# 04_FMC_HPC0.net
KiCad netlist of a schematic drawn in Altium Designer
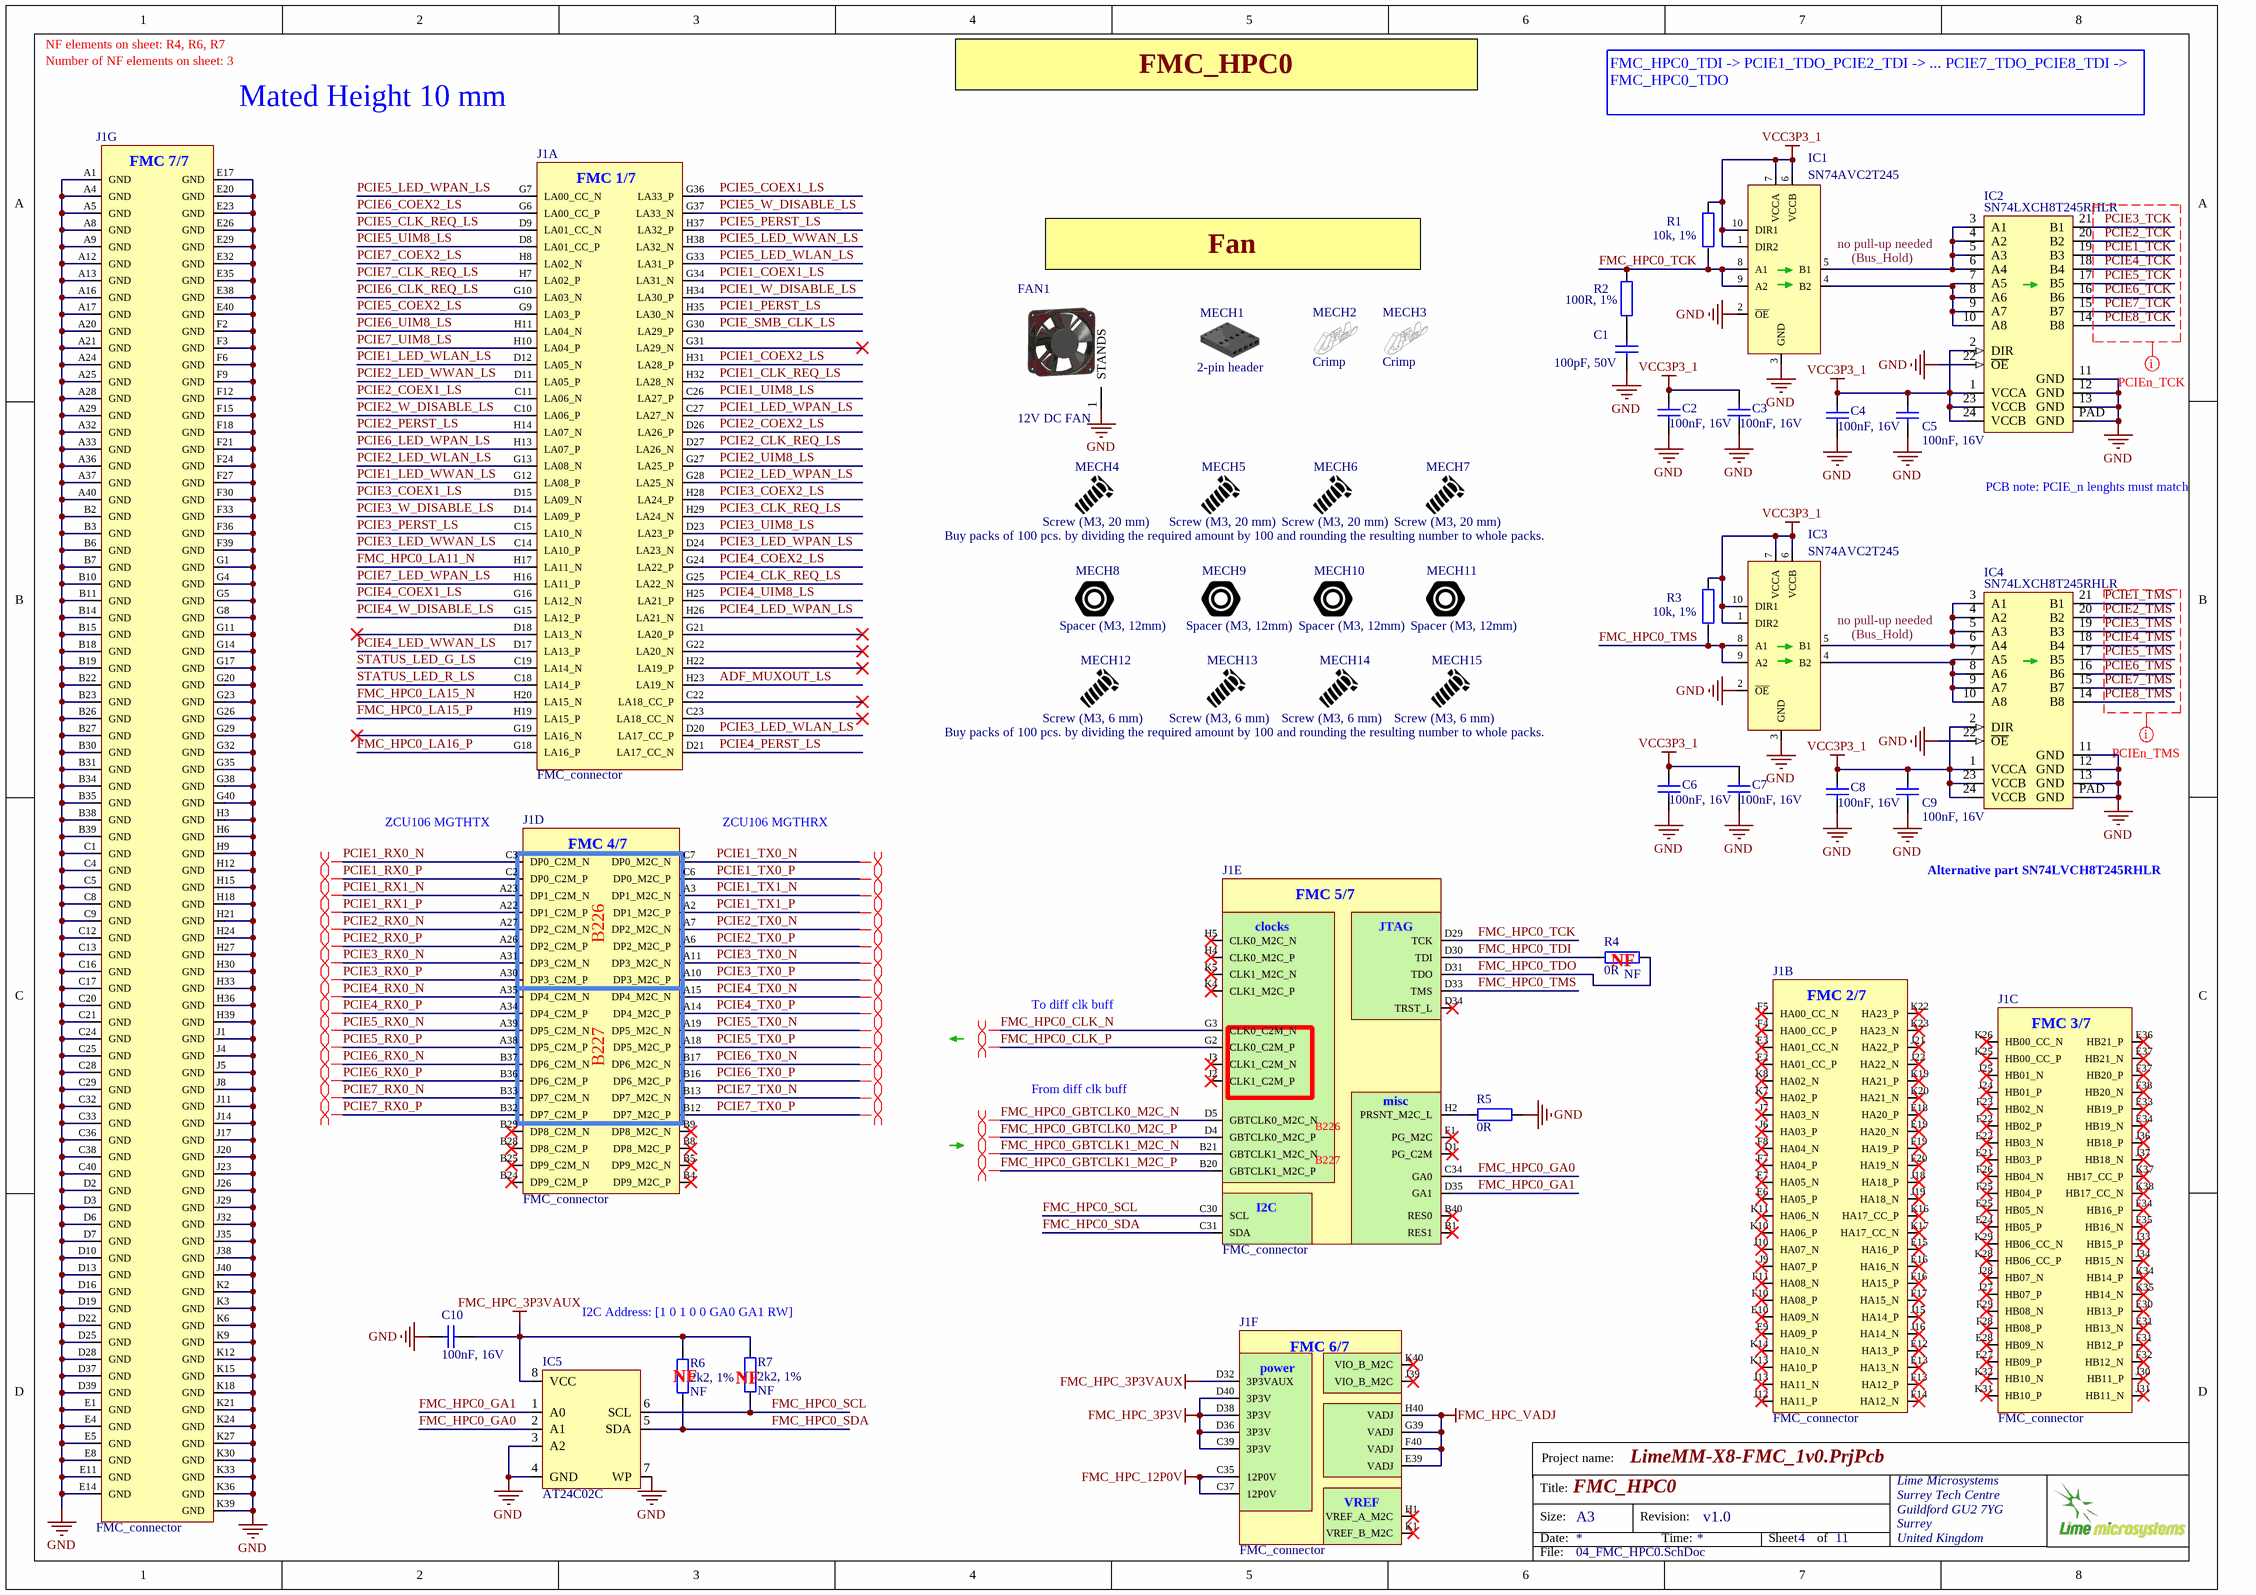
[diagram p0: 04_FMC_HPC0.SchDoc]

(export (version "E")
  (design (tool "Eeschema 10.0.6"))
  (components
    (comp (ref "C1")
      (value "100pF, 50V")
      (footprint "CAP0402")
      (fields (field (name "TOLERANCE") "±5%") (field (name "MANUFACTURER") "Yageo"))
      (libsource (lib "LimeMicroAltiumLib_schLib") (part "Cap_0402"))
    )
    (comp (ref "C2")
      (value "100nF, 16V")
      (footprint "CAP0402")
      (fields (field (name "TOLERANCE") "10 %") (field (name "MANUFACTURER") "Murata Electronics"))
      (libsource (lib "LimeFPGAboard_schLib") (part "Cap_0603"))
    )
    (comp (ref "C3")
      (value "100nF, 16V")
      (footprint "CAP0402")
      (fields (field (name "TOLERANCE") "10 %") (field (name "MANUFACTURER") "Murata Electronics"))
      (libsource (lib "LimeFPGAboard_schLib") (part "Cap_0603"))
    )
    (comp (ref "C4")
      (value "100nF, 16V")
      (footprint "CAP0402")
      (fields (field (name "TOLERANCE") "10 %") (field (name "MANUFACTURER") "Murata Electronics"))
      (libsource (lib "LimeFPGAboard_schLib") (part "Cap_0603"))
    )
    (comp (ref "C5")
      (value "100nF, 16V")
      (footprint "CAP0402")
      (fields (field (name "TOLERANCE") "10 %") (field (name "MANUFACTURER") "Murata Electronics"))
      (libsource (lib "LimeFPGAboard_schLib") (part "Cap_0603"))
    )
    (comp (ref "C6")
      (value "100nF, 16V")
      (footprint "CAP0402")
      (fields (field (name "TOLERANCE") "10 %") (field (name "MANUFACTURER") "Murata Electronics"))
      (libsource (lib "LimeFPGAboard_schLib") (part "Cap_0603"))
    )
    (comp (ref "C7")
      (value "100nF, 16V")
      (footprint "CAP0402")
      (fields (field (name "TOLERANCE") "10 %") (field (name "MANUFACTURER") "Murata Electronics"))
      (libsource (lib "LimeFPGAboard_schLib") (part "Cap_0603"))
    )
    (comp (ref "C8")
      (value "100nF, 16V")
      (footprint "CAP0402")
      (fields (field (name "TOLERANCE") "10 %") (field (name "MANUFACTURER") "Murata Electronics"))
      (libsource (lib "LimeFPGAboard_schLib") (part "Cap_0603"))
    )
    (comp (ref "C9")
      (value "100nF, 16V")
      (footprint "CAP0402")
      (fields (field (name "TOLERANCE") "10 %") (field (name "MANUFACTURER") "Murata Electronics"))
      (libsource (lib "LimeFPGAboard_schLib") (part "Cap_0603"))
    )
    (comp (ref "C10")
      (value "100nF, 16V")
      (footprint "CAP0402")
      (fields (field (name "TOLERANCE") "10 %") (field (name "MANUFACTURER") "Murata Electronics"))
      (libsource (lib "LimeFPGAboard_schLib") (part "Cap_0603"))
    )
    (comp (ref "FAN1")
      (value "12V DC FAN")
      (footprint "FAN_80mm")
      (fields (field (name "MANUFACTURER") "Sunon"))
      (libsource (lib "LimeMicroAltiumLib_schLib_r04") (part "12V_DC_FAN"))
    )
    (comp (ref "IC1")
      (value "SN74AVC2T245")
      (footprint "SN74AVC2T245RSWR")
      (fields (field (name "MANUFACTURER") "Texas Instruments"))
      (libsource (lib "*") (part "SN74AVC2T245"))
    )
    (comp (ref "IC2")
      (value "SN74LXCH8T245RHLR")
      (footprint "SN74LVC8T245RHLR_24-VQFN_LVL_SHIFTER")
      (fields (field (name "MANUFACTURER") "Texas Instruments"))
      (libsource (lib "*") (part "SN74LVC8T245RHLR_LVL_SHIFTER"))
    )
    (comp (ref "IC3")
      (value "SN74AVC2T245")
      (footprint "SN74AVC2T245RSWR")
      (fields (field (name "MANUFACTURER") "Texas Instruments"))
      (libsource (lib "*") (part "SN74AVC2T245"))
    )
    (comp (ref "IC4")
      (value "SN74LXCH8T245RHLR")
      (footprint "SN74LVC8T245RHLR_24-VQFN_LVL_SHIFTER")
      (fields (field (name "MANUFACTURER") "Texas Instruments"))
      (libsource (lib "*") (part "SN74LVC8T245RHLR_LVL_SHIFTER"))
    )
    (comp (ref "IC5")
      (value "AT24C02C")
      (footprint "SOIC127P600-8DL_v2")
      (fields (field (name "MANUFACTURER") "ATMEL"))
      (libsource (lib "LimeMicroAltiumLib_schLib") (part "AT24C02C-SSHM-B"))
    )
    (comp (ref "J1")
      (value "FMC_connector")
      (footprint "FMC_HPC_terminal_conn_ASP-134488-01")
      (fields (field (name "MANUFACTURER") "Samtec"))
      (libsource (lib "LimeMicroAltiumLib") (part "FMC_connector"))
    )
    (comp (ref "MECH1")
      (value "2-pin header")
      (fields (field (name "MANUFACTURER") "Molex"))
      (libsource (lib "LimeMicroAltiumLib_schLib_r05") (part "Universal_crimped_header"))
    )
    (comp (ref "MECH2")
      (value "Crimp")
      (fields (field (name "MANUFACTURER") "Molex"))
      (libsource (lib "LimeMicroAltiumLib_schLib_r05") (part "Universal_crimp"))
    )
    (comp (ref "MECH3")
      (value "Crimp")
      (fields (field (name "MANUFACTURER") "Molex"))
      (libsource (lib "LimeMicroAltiumLib_schLib_r05") (part "Universal_crimp"))
    )
    (comp (ref "MECH4")
      (value "Screw (M3, 20 mm)")
      (fields (field (name "MANUFACTURER") "TR Fastenings"))
      (libsource (lib "LimeMicroAltiumLib_schLib_r05") (part "Universal_mech_screw"))
    )
    (comp (ref "MECH5")
      (value "Screw (M3, 20 mm)")
      (fields
        (field (name "ASSEMBLY INFO") "Buy packs of 100 pcs. by dividing the required amount by 100 and rounding the resulting number to whole packs.")
        (field (name "MANUFACTURER") "TR Fastenings")
      )
      (libsource (lib "LimeMicroAltiumLib_schLib_r05") (part "Universal_mech_screw"))
    )
    (comp (ref "MECH6")
      (value "Screw (M3, 20 mm)")
      (fields (field (name "MANUFACTURER") "TR Fastenings"))
      (libsource (lib "LimeMicroAltiumLib_schLib_r05") (part "Universal_mech_screw"))
    )
    (comp (ref "MECH7")
      (value "Screw (M3, 20 mm)")
      (fields (field (name "MANUFACTURER") "TR Fastenings"))
      (libsource (lib "LimeMicroAltiumLib_schLib_r05") (part "Universal_mech_screw"))
    )
    (comp (ref "MECH8")
      (value "Spacer (M3, 12mm)")
      (fields (field (name "MANUFACTURER") "ETTINGER"))
      (libsource (lib "LimeMicroAltiumLib_schLib_r05") (part "Universal_mech_nut"))
    )
    (comp (ref "MECH9")
      (value "Spacer (M3, 12mm)")
      (fields (field (name "MANUFACTURER") "ETTINGER"))
      (libsource (lib "LimeMicroAltiumLib_schLib_r05") (part "Universal_mech_nut"))
    )
    (comp (ref "MECH10")
      (value "Spacer (M3, 12mm)")
      (fields (field (name "MANUFACTURER") "ETTINGER"))
      (libsource (lib "LimeMicroAltiumLib_schLib_r05") (part "Universal_mech_nut"))
    )
    (comp (ref "MECH11")
      (value "Spacer (M3, 12mm)")
      (fields (field (name "MANUFACTURER") "ETTINGER"))
      (libsource (lib "LimeMicroAltiumLib_schLib_r05") (part "Universal_mech_nut"))
    )
    (comp (ref "MECH12")
      (value "Screw (M3, 6 mm)")
      (fields (field (name "MANUFACTURER") "TR Fastenings"))
      (libsource (lib "LimeMicroAltiumLib_schLib_r05") (part "Universal_mech_screw"))
    )
    (comp (ref "MECH13")
      (value "Screw (M3, 6 mm)")
      (fields
        (field (name "ASSEMBLY INFO") "Buy packs of 100 pcs. by dividing the required amount by 100 and rounding the resulting number to whole packs.")
        (field (name "MANUFACTURER") "TR Fastenings")
      )
      (libsource (lib "LimeMicroAltiumLib_schLib_r05") (part "Universal_mech_screw"))
    )
    (comp (ref "MECH14")
      (value "Screw (M3, 6 mm)")
      (fields (field (name "MANUFACTURER") "TR Fastenings"))
      (libsource (lib "LimeMicroAltiumLib_schLib_r05") (part "Universal_mech_screw"))
    )
    (comp (ref "MECH15")
      (value "Screw (M3, 6 mm)")
      (fields (field (name "MANUFACTURER") "TR Fastenings"))
      (libsource (lib "LimeMicroAltiumLib_schLib_r05") (part "Universal_mech_screw"))
    )
    (comp (ref "R1")
      (value "10k, 1%")
      (footprint "RES0402")
      (fields (field (name "MANUFACTURER") "Yageo") (field (name "TOLERANCE") "±1%"))
      (libsource (lib "LimeMicroAltiumLib_schLib") (part "Res_0402"))
    )
    (comp (ref "R2")
      (value "100R, 1%")
      (footprint "RES0402")
      (fields (field (name "TOLERANCE") "±1%") (field (name "MANUFACTURER") "Stackpole Electronics Inc."))
      (libsource (lib "LimeFPGAboard_schLib") (part "Res_0402"))
    )
    (comp (ref "R3")
      (value "10k, 1%")
      (footprint "RES0402")
      (fields (field (name "MANUFACTURER") "Yageo") (field (name "TOLERANCE") "±1%"))
      (libsource (lib "LimeMicroAltiumLib_schLib") (part "Res_0402"))
    )
    (comp (ref "R4")
      (value "0R")
      (footprint "RES0402")
      (fields
        (field (name "ASSEMBLY INFO") "NF")
        (field (name "MANUFACTURER") "Yageo")
        (field (name "TOLERANCE") "Jumper")
      )
      (libsource (lib "") (part "Res_0402_1"))
    )
    (comp (ref "R5")
      (value "0R")
      (footprint "RES0402")
      (fields (field (name "MANUFACTURER") "Yageo") (field (name "TOLERANCE") "Jumper"))
      (libsource (lib "LimeMicroAltiumLib_schLib") (part "Res_0402"))
    )
    (comp (ref "R6")
      (value "2k2, 1%")
      (footprint "RES0402")
      (fields
        (field (name "ASSEMBLY INFO") "NF")
        (field (name "MANUFACTURER") "Stackpole Electronics Inc")
        (field (name "TOLERANCE") "±1%")
      )
      (libsource (lib "") (part "Res_0402_1"))
    )
    (comp (ref "R7")
      (value "2k2, 1%")
      (footprint "RES0402")
      (fields
        (field (name "ASSEMBLY INFO") "NF")
        (field (name "MANUFACTURER") "Stackpole Electronics Inc")
        (field (name "TOLERANCE") "±1%")
      )
      (libsource (lib "") (part "Res_0402_1"))
    )
  )
  (nets
    (net (code "1") (name "/ADF_MUXOUT_LS") (class "Default")
      (node (ref "J1") (pin "H23") (pinfunction "LA19_N_H23") (pintype "passive"))
    )
    (net (code "2") (name "/FMC_HPC0_CLK_N") (class "Default")
      (node (ref "J1") (pin "G3") (pinfunction "CLK0_C2M_N_G3") (pintype "passive"))
    )
    (net (code "3") (name "/FMC_HPC0_CLK_P") (class "Default")
      (node (ref "J1") (pin "G2") (pinfunction "CLK0_C2M_P_G2") (pintype "passive"))
    )
    (net (code "4") (name "/FMC_HPC0_GA0") (class "Default")
      (node (ref "IC5") (pin "2") (pinfunction "A1_2") (pintype "passive"))
      (node (ref "J1") (pin "C34") (pinfunction "GA0_C34") (pintype "passive"))
    )
    (net (code "5") (name "/FMC_HPC0_GA1") (class "Default")
      (node (ref "IC5") (pin "1") (pinfunction "A0_1") (pintype "passive"))
      (node (ref "J1") (pin "D35") (pinfunction "GA1_D35") (pintype "passive"))
    )
    (net (code "6") (name "/FMC_HPC0_GBTCLK0_M2C_N") (class "Default")
      (node (ref "J1") (pin "D5") (pinfunction "GBTCLK0_M2C_N_D5") (pintype "passive"))
    )
    (net (code "7") (name "/FMC_HPC0_GBTCLK0_M2C_P") (class "Default")
      (node (ref "J1") (pin "D4") (pinfunction "GBTCLK0_M2C_P_D4") (pintype "passive"))
    )
    (net (code "8") (name "/FMC_HPC0_GBTCLK1_M2C_N") (class "Default")
      (node (ref "J1") (pin "B21") (pinfunction "GBTCLK1_M2C_N_B21") (pintype "passive"))
    )
    (net (code "9") (name "/FMC_HPC0_GBTCLK1_M2C_P") (class "Default")
      (node (ref "J1") (pin "B20") (pinfunction "GBTCLK1_M2C_P_B20") (pintype "passive"))
    )
    (net (code "10") (name "/FMC_HPC0_LA11_N") (class "Default")
      (node (ref "J1") (pin "H17") (pinfunction "LA11_N_H17") (pintype "passive"))
    )
    (net (code "11") (name "/FMC_HPC0_LA15_N") (class "Default")
      (node (ref "J1") (pin "H20") (pinfunction "LA15_N_H20") (pintype "passive"))
    )
    (net (code "12") (name "/FMC_HPC0_LA15_P") (class "Default")
      (node (ref "J1") (pin "H19") (pinfunction "LA15_P_H19") (pintype "passive"))
    )
    (net (code "13") (name "/FMC_HPC0_LA16_P") (class "Default")
      (node (ref "J1") (pin "G18") (pinfunction "LA16_P_G18") (pintype "passive"))
    )
    (net (code "14") (name "/FMC_HPC0_SCL") (class "Default")
      (node (ref "IC5") (pin "6") (pinfunction "SCL_6") (pintype "passive"))
      (node (ref "J1") (pin "C30") (pinfunction "SCL_C30") (pintype "passive"))
      (node (ref "R7") (pin "2") (pinfunction "2_2") (pintype "passive"))
    )
    (net (code "15") (name "/FMC_HPC0_SDA") (class "Default")
      (node (ref "IC5") (pin "5") (pinfunction "SDA_5") (pintype "passive"))
      (node (ref "J1") (pin "C31") (pinfunction "SDA_C31") (pintype "passive"))
      (node (ref "R6") (pin "2") (pinfunction "2_2") (pintype "passive"))
    )
    (net (code "16") (name "/FMC_HPC0_TCK") (class "Default")
      (node (ref "IC1") (pin "8") (pinfunction "A1_8") (pintype "passive"))
      (node (ref "IC1") (pin "9") (pinfunction "A2_9") (pintype "passive"))
      (node (ref "J1") (pin "D29") (pinfunction "TCK_D29") (pintype "passive"))
      (node (ref "R1") (pin "2") (pinfunction "2_2") (pintype "passive"))
      (node (ref "R2") (pin "2") (pinfunction "2_2") (pintype "passive"))
    )
    (net (code "17") (name "/FMC_HPC0_TDI") (class "Default")
      (node (ref "J1") (pin "D30") (pinfunction "TDI_D30") (pintype "passive"))
      (node (ref "R4") (pin "2") (pinfunction "2_2") (pintype "passive"))
    )
    (net (code "18") (name "/FMC_HPC0_TDO") (class "Default")
      (node (ref "J1") (pin "D31") (pinfunction "TDO_D31") (pintype "passive"))
      (node (ref "R4") (pin "1") (pinfunction "1_1") (pintype "passive"))
    )
    (net (code "19") (name "/FMC_HPC0_TMS") (class "Default")
      (node (ref "IC3") (pin "8") (pinfunction "A1_8") (pintype "passive"))
      (node (ref "IC3") (pin "9") (pinfunction "A2_9") (pintype "passive"))
      (node (ref "J1") (pin "D33") (pinfunction "TMS_D33") (pintype "passive"))
      (node (ref "R3") (pin "2") (pinfunction "2_2") (pintype "passive"))
    )
    (net (code "20") (name "/PCIE1_CLK_REQ_LS") (class "Default")
      (node (ref "J1") (pin "H32") (pinfunction "LA28_N_H32") (pintype "passive"))
    )
    (net (code "21") (name "/PCIE1_COEX1_LS") (class "Default")
      (node (ref "J1") (pin "G34") (pinfunction "LA31_N_G34") (pintype "passive"))
    )
    (net (code "22") (name "/PCIE1_COEX2_LS") (class "Default")
      (node (ref "J1") (pin "H31") (pinfunction "LA28_P_H31") (pintype "passive"))
    )
    (net (code "23") (name "/PCIE1_LED_WLAN_LS") (class "Default")
      (node (ref "J1") (pin "D12") (pinfunction "LA05_N_D12") (pintype "passive"))
    )
    (net (code "24") (name "/PCIE1_LED_WPAN_LS") (class "Default")
      (node (ref "J1") (pin "C27") (pinfunction "LA27_N_C27") (pintype "passive"))
    )
    (net (code "25") (name "/PCIE1_LED_WWAN_LS") (class "Default")
      (node (ref "J1") (pin "G12") (pinfunction "LA08_P_G12") (pintype "passive"))
    )
    (net (code "26") (name "/PCIE1_PERST_LS") (class "Default")
      (node (ref "J1") (pin "H35") (pinfunction "LA30_N_H35") (pintype "passive"))
    )
    (net (code "27") (name "/PCIE1_RX0_N") (class "Default")
      (node (ref "J1") (pin "C3") (pinfunction "DP0_C2M_N_C3") (pintype "passive"))
    )
    (net (code "28") (name "/PCIE1_RX0_P") (class "Default")
      (node (ref "J1") (pin "C2") (pinfunction "DP0_C2M_P_C2") (pintype "passive"))
    )
    (net (code "29") (name "/PCIE1_RX1_N") (class "Default")
      (node (ref "J1") (pin "A23") (pinfunction "DP1_C2M_N_A23") (pintype "passive"))
    )
    (net (code "30") (name "/PCIE1_RX1_P") (class "Default")
      (node (ref "J1") (pin "A22") (pinfunction "DP1_C2M_P_A22") (pintype "passive"))
    )
    (net (code "31") (name "/PCIE1_TCK") (class "Default")
      (node (ref "IC2") (pin "19") (pinfunction "B3_19") (pintype "bidirectional"))
    )
    (net (code "32") (name "/PCIE1_TMS") (class "Default")
      (node (ref "IC4") (pin "21") (pinfunction "B1_21") (pintype "bidirectional"))
    )
    (net (code "33") (name "/PCIE1_TX0_N") (class "Default")
      (node (ref "J1") (pin "C7") (pinfunction "DP0_M2C_N_C7") (pintype "passive"))
    )
    (net (code "34") (name "/PCIE1_TX0_P") (class "Default")
      (node (ref "J1") (pin "C6") (pinfunction "DP0_M2C_P_C6") (pintype "passive"))
    )
    (net (code "35") (name "/PCIE1_TX1_N") (class "Default")
      (node (ref "J1") (pin "A3") (pinfunction "DP1_M2C_N_A3") (pintype "passive"))
    )
    (net (code "36") (name "/PCIE1_TX1_P") (class "Default")
      (node (ref "J1") (pin "A2") (pinfunction "DP1_M2C_P_A2") (pintype "passive"))
    )
    (net (code "37") (name "/PCIE1_UIM8_LS") (class "Default")
      (node (ref "J1") (pin "C26") (pinfunction "LA27_P_C26") (pintype "passive"))
    )
    (net (code "38") (name "/PCIE1_W_DISABLE_LS") (class "Default")
      (node (ref "J1") (pin "H34") (pinfunction "LA30_P_H34") (pintype "passive"))
    )
    (net (code "39") (name "/PCIE2_CLK_REQ_LS") (class "Default")
      (node (ref "J1") (pin "D27") (pinfunction "LA26_N_D27") (pintype "passive"))
    )
    (net (code "40") (name "/PCIE2_COEX1_LS") (class "Default")
      (node (ref "J1") (pin "C11") (pinfunction "LA06_N_C11") (pintype "passive"))
    )
    (net (code "41") (name "/PCIE2_COEX2_LS") (class "Default")
      (node (ref "J1") (pin "D26") (pinfunction "LA26_P_D26") (pintype "passive"))
    )
    (net (code "42") (name "/PCIE2_LED_WLAN_LS") (class "Default")
      (node (ref "J1") (pin "G13") (pinfunction "LA08_N_G13") (pintype "passive"))
    )
    (net (code "43") (name "/PCIE2_LED_WPAN_LS") (class "Default")
      (node (ref "J1") (pin "G28") (pinfunction "LA25_N_G28") (pintype "passive"))
    )
    (net (code "44") (name "/PCIE2_LED_WWAN_LS") (class "Default")
      (node (ref "J1") (pin "D11") (pinfunction "LA05_P_D11") (pintype "passive"))
    )
    (net (code "45") (name "/PCIE2_PERST_LS") (class "Default")
      (node (ref "J1") (pin "H14") (pinfunction "LA07_N_H14") (pintype "passive"))
    )
    (net (code "46") (name "/PCIE2_RX0_N") (class "Default")
      (node (ref "J1") (pin "A27") (pinfunction "DP2_C2M_N_A27") (pintype "passive"))
    )
    (net (code "47") (name "/PCIE2_RX0_P") (class "Default")
      (node (ref "J1") (pin "A26") (pinfunction "DP2_C2M_P_A26") (pintype "passive"))
    )
    (net (code "48") (name "/PCIE2_TCK") (class "Default")
      (node (ref "IC2") (pin "20") (pinfunction "B2_20") (pintype "bidirectional"))
    )
    (net (code "49") (name "/PCIE2_TMS") (class "Default")
      (node (ref "IC4") (pin "20") (pinfunction "B2_20") (pintype "bidirectional"))
    )
    (net (code "50") (name "/PCIE2_TX0_N") (class "Default")
      (node (ref "J1") (pin "A7") (pinfunction "DP2_M2C_N_A7") (pintype "passive"))
    )
    (net (code "51") (name "/PCIE2_TX0_P") (class "Default")
      (node (ref "J1") (pin "A6") (pinfunction "DP2_M2C_P_A6") (pintype "passive"))
    )
    (net (code "52") (name "/PCIE2_UIM8_LS") (class "Default")
      (node (ref "J1") (pin "G27") (pinfunction "LA25_P_G27") (pintype "passive"))
    )
    (net (code "53") (name "/PCIE2_W_DISABLE_LS") (class "Default")
      (node (ref "J1") (pin "C10") (pinfunction "LA06_P_C10") (pintype "passive"))
    )
    (net (code "54") (name "/PCIE3_CLK_REQ_LS") (class "Default")
      (node (ref "J1") (pin "H29") (pinfunction "LA24_N_H29") (pintype "passive"))
    )
    (net (code "55") (name "/PCIE3_COEX1_LS") (class "Default")
      (node (ref "J1") (pin "D15") (pinfunction "LA09_N_D15") (pintype "passive"))
    )
    (net (code "56") (name "/PCIE3_COEX2_LS") (class "Default")
      (node (ref "J1") (pin "H28") (pinfunction "LA24_P_H28") (pintype "passive"))
    )
    (net (code "57") (name "/PCIE3_LED_WLAN_LS") (class "Default")
      (node (ref "J1") (pin "D20") (pinfunction "LA17_CC_P_D20") (pintype "passive"))
    )
    (net (code "58") (name "/PCIE3_LED_WPAN_LS") (class "Default")
      (node (ref "J1") (pin "D24") (pinfunction "LA23_N_D24") (pintype "passive"))
    )
    (net (code "59") (name "/PCIE3_LED_WWAN_LS") (class "Default")
      (node (ref "J1") (pin "C14") (pinfunction "LA10_P_C14") (pintype "passive"))
    )
    (net (code "60") (name "/PCIE3_PERST_LS") (class "Default")
      (node (ref "J1") (pin "C15") (pinfunction "LA10_N_C15") (pintype "passive"))
    )
    (net (code "61") (name "/PCIE3_RX0_N") (class "Default")
      (node (ref "J1") (pin "A31") (pinfunction "DP3_C2M_N_A31") (pintype "passive"))
    )
    (net (code "62") (name "/PCIE3_RX0_P") (class "Default")
      (node (ref "J1") (pin "A30") (pinfunction "DP3_C2M_P_A30") (pintype "passive"))
    )
    (net (code "63") (name "/PCIE3_TCK") (class "Default")
      (node (ref "IC2") (pin "21") (pinfunction "B1_21") (pintype "bidirectional"))
    )
    (net (code "64") (name "/PCIE3_TMS") (class "Default")
      (node (ref "IC4") (pin "19") (pinfunction "B3_19") (pintype "bidirectional"))
    )
    (net (code "65") (name "/PCIE3_TX0_N") (class "Default")
      (node (ref "J1") (pin "A11") (pinfunction "DP3_M2C_N_A11") (pintype "passive"))
    )
    (net (code "66") (name "/PCIE3_TX0_P") (class "Default")
      (node (ref "J1") (pin "A10") (pinfunction "DP3_M2C_P_A10") (pintype "passive"))
    )
    (net (code "67") (name "/PCIE3_UIM8_LS") (class "Default")
      (node (ref "J1") (pin "D23") (pinfunction "LA23_P_D23") (pintype "passive"))
    )
    (net (code "68") (name "/PCIE3_W_DISABLE_LS") (class "Default")
      (node (ref "J1") (pin "D14") (pinfunction "LA09_P_D14") (pintype "passive"))
    )
    (net (code "69") (name "/PCIE4_CLK_REQ_LS") (class "Default")
      (node (ref "J1") (pin "G25") (pinfunction "LA22_N_G25") (pintype "passive"))
    )
    (net (code "70") (name "/PCIE4_COEX1_LS") (class "Default")
      (node (ref "J1") (pin "G16") (pinfunction "LA12_N_G16") (pintype "passive"))
    )
    (net (code "71") (name "/PCIE4_COEX2_LS") (class "Default")
      (node (ref "J1") (pin "G24") (pinfunction "LA22_P_G24") (pintype "passive"))
    )
    (net (code "72") (name "/PCIE4_LED_WPAN_LS") (class "Default")
      (node (ref "J1") (pin "H26") (pinfunction "LA21_N_H26") (pintype "passive"))
    )
    (net (code "73") (name "/PCIE4_LED_WWAN_LS") (class "Default")
      (node (ref "J1") (pin "D17") (pinfunction "LA13_P_D17") (pintype "passive"))
    )
    (net (code "74") (name "/PCIE4_PERST_LS") (class "Default")
      (node (ref "J1") (pin "D21") (pinfunction "LA17_CC_N_D21") (pintype "passive"))
    )
    (net (code "75") (name "/PCIE4_RX0_N") (class "Default")
      (node (ref "J1") (pin "A35") (pinfunction "DP4_C2M_N_A35") (pintype "passive"))
    )
    (net (code "76") (name "/PCIE4_RX0_P") (class "Default")
      (node (ref "J1") (pin "A34") (pinfunction "DP4_C2M_P_A34") (pintype "passive"))
    )
    (net (code "77") (name "/PCIE4_TCK") (class "Default")
      (node (ref "IC2") (pin "18") (pinfunction "B4_18") (pintype "bidirectional"))
    )
    (net (code "78") (name "/PCIE4_TMS") (class "Default")
      (node (ref "IC4") (pin "18") (pinfunction "B4_18") (pintype "bidirectional"))
    )
    (net (code "79") (name "/PCIE4_TX0_N") (class "Default")
      (node (ref "J1") (pin "A15") (pinfunction "DP4_M2C_N_A15") (pintype "passive"))
    )
    (net (code "80") (name "/PCIE4_TX0_P") (class "Default")
      (node (ref "J1") (pin "A14") (pinfunction "DP4_M2C_P_A14") (pintype "passive"))
    )
    (net (code "81") (name "/PCIE4_UIM8_LS") (class "Default")
      (node (ref "J1") (pin "H25") (pinfunction "LA21_P_H25") (pintype "passive"))
    )
    (net (code "82") (name "/PCIE4_W_DISABLE_LS") (class "Default")
      (node (ref "J1") (pin "G15") (pinfunction "LA12_P_G15") (pintype "passive"))
    )
    (net (code "83") (name "/PCIE5_CLK_REQ_LS") (class "Default")
      (node (ref "J1") (pin "D9") (pinfunction "LA01_CC_N_D9") (pintype "passive"))
    )
    (net (code "84") (name "/PCIE5_COEX1_LS") (class "Default")
      (node (ref "J1") (pin "G36") (pinfunction "LA33_P_G36") (pintype "passive"))
    )
    (net (code "85") (name "/PCIE5_COEX2_LS") (class "Default")
      (node (ref "J1") (pin "G9") (pinfunction "LA03_P_G9") (pintype "passive"))
    )
    (net (code "86") (name "/PCIE5_LED_WLAN_LS") (class "Default")
      (node (ref "J1") (pin "G33") (pinfunction "LA31_P_G33") (pintype "passive"))
    )
    (net (code "87") (name "/PCIE5_LED_WPAN_LS") (class "Default")
      (node (ref "J1") (pin "G7") (pinfunction "LA00_CC_N_G7") (pintype "passive"))
    )
    (net (code "88") (name "/PCIE5_LED_WWAN_LS") (class "Default")
      (node (ref "J1") (pin "H38") (pinfunction "LA32_N_H38") (pintype "passive"))
    )
    (net (code "89") (name "/PCIE5_PERST_LS") (class "Default")
      (node (ref "J1") (pin "H37") (pinfunction "LA32_P_H37") (pintype "passive"))
    )
    (net (code "90") (name "/PCIE5_RX0_N") (class "Default")
      (node (ref "J1") (pin "A39") (pinfunction "DP5_C2M_N_A39") (pintype "passive"))
    )
    (net (code "91") (name "/PCIE5_RX0_P") (class "Default")
      (node (ref "J1") (pin "A38") (pinfunction "DP5_C2M_P_A38") (pintype "passive"))
    )
    (net (code "92") (name "/PCIE5_TCK") (class "Default")
      (node (ref "IC2") (pin "17") (pinfunction "B5_17") (pintype "bidirectional"))
    )
    (net (code "93") (name "/PCIE5_TMS") (class "Default")
      (node (ref "IC4") (pin "17") (pinfunction "B5_17") (pintype "bidirectional"))
    )
    (net (code "94") (name "/PCIE5_TX0_N") (class "Default")
      (node (ref "J1") (pin "A19") (pinfunction "DP5_M2C_N_A19") (pintype "passive"))
    )
    (net (code "95") (name "/PCIE5_TX0_P") (class "Default")
      (node (ref "J1") (pin "A18") (pinfunction "DP5_M2C_P_A18") (pintype "passive"))
    )
    (net (code "96") (name "/PCIE5_UIM8_LS") (class "Default")
      (node (ref "J1") (pin "D8") (pinfunction "LA01_CC_P_D8") (pintype "passive"))
    )
    (net (code "97") (name "/PCIE5_W_DISABLE_LS") (class "Default")
      (node (ref "J1") (pin "G37") (pinfunction "LA33_N_G37") (pintype "passive"))
    )
    (net (code "98") (name "/PCIE6_CLK_REQ_LS") (class "Default")
      (node (ref "J1") (pin "G10") (pinfunction "LA03_N_G10") (pintype "passive"))
    )
    (net (code "99") (name "/PCIE6_COEX2_LS") (class "Default")
      (node (ref "J1") (pin "G6") (pinfunction "LA00_CC_P_G6") (pintype "passive"))
    )
    (net (code "100") (name "/PCIE6_LED_WPAN_LS") (class "Default")
      (node (ref "J1") (pin "H13") (pinfunction "LA07_P_H13") (pintype "passive"))
    )
    (net (code "101") (name "/PCIE6_RX0_N") (class "Default")
      (node (ref "J1") (pin "B37") (pinfunction "DP6_C2M_N_B37") (pintype "passive"))
    )
    (net (code "102") (name "/PCIE6_RX0_P") (class "Default")
      (node (ref "J1") (pin "B36") (pinfunction "DP6_C2M_P_B36") (pintype "passive"))
    )
    (net (code "103") (name "/PCIE6_TCK") (class "Default")
      (node (ref "IC2") (pin "16") (pinfunction "B6_16") (pintype "bidirectional"))
    )
    (net (code "104") (name "/PCIE6_TMS") (class "Default")
      (node (ref "IC4") (pin "16") (pinfunction "B6_16") (pintype "bidirectional"))
    )
    (net (code "105") (name "/PCIE6_TX0_N") (class "Default")
      (node (ref "J1") (pin "B17") (pinfunction "DP6_M2C_N_B17") (pintype "passive"))
    )
    (net (code "106") (name "/PCIE6_TX0_P") (class "Default")
      (node (ref "J1") (pin "B16") (pinfunction "DP6_M2C_P_B16") (pintype "passive"))
    )
    (net (code "107") (name "/PCIE6_UIM8_LS") (class "Default")
      (node (ref "J1") (pin "H11") (pinfunction "LA04_N_H11") (pintype "passive"))
    )
    (net (code "108") (name "/PCIE7_CLK_REQ_LS") (class "Default")
      (node (ref "J1") (pin "H7") (pinfunction "LA02_P_H7") (pintype "passive"))
    )
    (net (code "109") (name "/PCIE7_COEX2_LS") (class "Default")
      (node (ref "J1") (pin "H8") (pinfunction "LA02_N_H8") (pintype "passive"))
    )
    (net (code "110") (name "/PCIE7_LED_WPAN_LS") (class "Default")
      (node (ref "J1") (pin "H16") (pinfunction "LA11_P_H16") (pintype "passive"))
    )
    (net (code "111") (name "/PCIE7_RX0_N") (class "Default")
      (node (ref "J1") (pin "B33") (pinfunction "DP7_C2M_N_B33") (pintype "passive"))
    )
    (net (code "112") (name "/PCIE7_RX0_P") (class "Default")
      (node (ref "J1") (pin "B32") (pinfunction "DP7_C2M_P_B32") (pintype "passive"))
    )
    (net (code "113") (name "/PCIE7_TCK") (class "Default")
      (node (ref "IC2") (pin "15") (pinfunction "B7_15") (pintype "bidirectional"))
    )
    (net (code "114") (name "/PCIE7_TMS") (class "Default")
      (node (ref "IC4") (pin "15") (pinfunction "B7_15") (pintype "bidirectional"))
    )
    (net (code "115") (name "/PCIE7_TX0_N") (class "Default")
      (node (ref "J1") (pin "B13") (pinfunction "DP7_M2C_N_B13") (pintype "passive"))
    )
    (net (code "116") (name "/PCIE7_TX0_P") (class "Default")
      (node (ref "J1") (pin "B12") (pinfunction "DP7_M2C_P_B12") (pintype "passive"))
    )
    (net (code "117") (name "/PCIE7_UIM8_LS") (class "Default")
      (node (ref "J1") (pin "H10") (pinfunction "LA04_P_H10") (pintype "passive"))
    )
    (net (code "118") (name "/PCIE8_TCK") (class "Default")
      (node (ref "IC2") (pin "14") (pinfunction "B8_14") (pintype "bidirectional"))
    )
    (net (code "119") (name "/PCIE8_TMS") (class "Default")
      (node (ref "IC4") (pin "14") (pinfunction "B8_14") (pintype "bidirectional"))
    )
    (net (code "120") (name "/PCIE_SMB_CLK_LS") (class "Default")
      (node (ref "J1") (pin "G30") (pinfunction "LA29_P_G30") (pintype "passive"))
    )
    (net (code "121") (name "/STATUS_LED_G_LS") (class "Default")
      (node (ref "J1") (pin "C19") (pinfunction "LA14_N_C19") (pintype "passive"))
    )
    (net (code "122") (name "/STATUS_LED_R_LS") (class "Default")
      (node (ref "J1") (pin "C18") (pinfunction "LA14_P_C18") (pintype "passive"))
    )
    (net (code "123") (name "FMC_HPC_3P3V") (class "Default")
      (node (ref "J1") (pin "C39") (pinfunction "3P3V_C39") (pintype "passive"))
      (node (ref "J1") (pin "D36") (pinfunction "3P3V_D36") (pintype "passive"))
      (node (ref "J1") (pin "D38") (pinfunction "3P3V_D38") (pintype "passive"))
      (node (ref "J1") (pin "D40") (pinfunction "3P3V_D40") (pintype "passive"))
    )
    (net (code "124") (name "FMC_HPC_3P3VAUX") (class "Default")
      (node (ref "C10") (pin "1") (pinfunction "1_1") (pintype "passive"))
      (node (ref "IC5") (pin "8") (pinfunction "VCC_8") (pintype "passive"))
      (node (ref "J1") (pin "D32") (pinfunction "3P3VAUX_D32") (pintype "passive"))
      (node (ref "R6") (pin "1") (pinfunction "1_1") (pintype "passive"))
      (node (ref "R7") (pin "1") (pinfunction "1_1") (pintype "passive"))
    )
    (net (code "125") (name "FMC_HPC_12P0V") (class "Default")
      (node (ref "J1") (pin "C35") (pinfunction "12P0V_C35") (pintype "passive"))
      (node (ref "J1") (pin "C37") (pinfunction "12P0V_C37") (pintype "passive"))
    )
    (net (code "126") (name "FMC_HPC_VADJ") (class "Default")
      (node (ref "J1") (pin "E39") (pinfunction "VADJ_E39") (pintype "passive"))
      (node (ref "J1") (pin "F40") (pinfunction "VADJ_F40") (pintype "passive"))
      (node (ref "J1") (pin "G39") (pinfunction "VADJ_G39") (pintype "passive"))
      (node (ref "J1") (pin "H40") (pinfunction "VADJ_H40") (pintype "passive"))
    )
    (net (code "127") (name "GND") (class "Default")
      (node (ref "C1") (pin "2") (pinfunction "2_2") (pintype "passive"))
      (node (ref "C10") (pin "2") (pinfunction "2_2") (pintype "passive"))
      (node (ref "C2") (pin "1") (pinfunction "1_1") (pintype "passive"))
      (node (ref "C3") (pin "1") (pinfunction "1_1") (pintype "passive"))
      (node (ref "C4") (pin "1") (pinfunction "1_1") (pintype "passive"))
      (node (ref "C5") (pin "1") (pinfunction "1_1") (pintype "passive"))
      (node (ref "C6") (pin "1") (pinfunction "1_1") (pintype "passive"))
      (node (ref "C7") (pin "1") (pinfunction "1_1") (pintype "passive"))
      (node (ref "C8") (pin "1") (pinfunction "1_1") (pintype "passive"))
      (node (ref "C9") (pin "1") (pinfunction "1_1") (pintype "passive"))
      (node (ref "FAN1") (pin "1") (pinfunction "STANDS_1") (pintype "passive"))
      (node (ref "IC1") (pin "2") (pinfunction "~{OE}_2") (pintype "passive"))
      (node (ref "IC1") (pin "3") (pinfunction "GND_3") (pintype "passive"))
      (node (ref "IC2") (pin "11") (pinfunction "GND_11") (pintype "passive"))
      (node (ref "IC2") (pin "12") (pinfunction "GND_12") (pintype "passive"))
      (node (ref "IC2") (pin "13") (pinfunction "GND_13") (pintype "passive"))
      (node (ref "IC2") (pin "22") (pinfunction "~{OE}_22") (pintype "input"))
      (node (ref "IC2") (pin "PAD") (pinfunction "GND_PAD") (pintype "passive"))
      (node (ref "IC3") (pin "2") (pinfunction "~{OE}_2") (pintype "passive"))
      (node (ref "IC3") (pin "3") (pinfunction "GND_3") (pintype "passive"))
      (node (ref "IC4") (pin "11") (pinfunction "GND_11") (pintype "passive"))
      (node (ref "IC4") (pin "12") (pinfunction "GND_12") (pintype "passive"))
      (node (ref "IC4") (pin "13") (pinfunction "GND_13") (pintype "passive"))
      (node (ref "IC4") (pin "22") (pinfunction "~{OE}_22") (pintype "input"))
      (node (ref "IC4") (pin "PAD") (pinfunction "GND_PAD") (pintype "passive"))
      (node (ref "IC5") (pin "3") (pinfunction "A2_3") (pintype "passive"))
      (node (ref "IC5") (pin "4") (pinfunction "GND_4") (pintype "passive"))
      (node (ref "IC5") (pin "7") (pinfunction "WP_7") (pintype "passive"))
      (node (ref "J1") (pin "A1") (pinfunction "GND_A1") (pintype "passive"))
      (node (ref "J1") (pin "A12") (pinfunction "GND_A12") (pintype "passive"))
      (node (ref "J1") (pin "A13") (pinfunction "GND_A13") (pintype "passive"))
      (node (ref "J1") (pin "A16") (pinfunction "GND_A16") (pintype "passive"))
      (node (ref "J1") (pin "A17") (pinfunction "GND_A17") (pintype "passive"))
      (node (ref "J1") (pin "A20") (pinfunction "GND_A20") (pintype "passive"))
      (node (ref "J1") (pin "A21") (pinfunction "GND_A21") (pintype "passive"))
      (node (ref "J1") (pin "A24") (pinfunction "GND_A24") (pintype "passive"))
      (node (ref "J1") (pin "A25") (pinfunction "GND_A25") (pintype "passive"))
      (node (ref "J1") (pin "A28") (pinfunction "GND_A28") (pintype "passive"))
      (node (ref "J1") (pin "A29") (pinfunction "GND_A29") (pintype "passive"))
      (node (ref "J1") (pin "A32") (pinfunction "GND_A32") (pintype "passive"))
      (node (ref "J1") (pin "A33") (pinfunction "GND_A33") (pintype "passive"))
      (node (ref "J1") (pin "A36") (pinfunction "GND_A36") (pintype "passive"))
      (node (ref "J1") (pin "A37") (pinfunction "GND_A37") (pintype "passive"))
      (node (ref "J1") (pin "A4") (pinfunction "GND_A4") (pintype "passive"))
      (node (ref "J1") (pin "A40") (pinfunction "GND_A40") (pintype "passive"))
      (node (ref "J1") (pin "A5") (pinfunction "GND_A5") (pintype "passive"))
      (node (ref "J1") (pin "A8") (pinfunction "GND_A8") (pintype "passive"))
      (node (ref "J1") (pin "A9") (pinfunction "GND_A9") (pintype "passive"))
      (node (ref "J1") (pin "B10") (pinfunction "GND_B10") (pintype "passive"))
      (node (ref "J1") (pin "B11") (pinfunction "GND_B11") (pintype "passive"))
      (node (ref "J1") (pin "B14") (pinfunction "GND_B14") (pintype "passive"))
      (node (ref "J1") (pin "B15") (pinfunction "GND_B15") (pintype "passive"))
      (node (ref "J1") (pin "B18") (pinfunction "GND_B18") (pintype "passive"))
      (node (ref "J1") (pin "B19") (pinfunction "GND_B19") (pintype "passive"))
      (node (ref "J1") (pin "B2") (pinfunction "GND_B2") (pintype "passive"))
      (node (ref "J1") (pin "B22") (pinfunction "GND_B22") (pintype "passive"))
      (node (ref "J1") (pin "B23") (pinfunction "GND_B23") (pintype "passive"))
      (node (ref "J1") (pin "B26") (pinfunction "GND_B26") (pintype "passive"))
      (node (ref "J1") (pin "B27") (pinfunction "GND_B27") (pintype "passive"))
      (node (ref "J1") (pin "B3") (pinfunction "GND_B3") (pintype "passive"))
      (node (ref "J1") (pin "B30") (pinfunction "GND_B30") (pintype "passive"))
      (node (ref "J1") (pin "B31") (pinfunction "GND_B31") (pintype "passive"))
      (node (ref "J1") (pin "B34") (pinfunction "GND_B34") (pintype "passive"))
      (node (ref "J1") (pin "B35") (pinfunction "GND_B35") (pintype "passive"))
      (node (ref "J1") (pin "B38") (pinfunction "GND_B38") (pintype "passive"))
      (node (ref "J1") (pin "B39") (pinfunction "GND_B39") (pintype "passive"))
      (node (ref "J1") (pin "B6") (pinfunction "GND_B6") (pintype "passive"))
      (node (ref "J1") (pin "B7") (pinfunction "GND_B7") (pintype "passive"))
      (node (ref "J1") (pin "C1") (pinfunction "GND_C1") (pintype "passive"))
      (node (ref "J1") (pin "C12") (pinfunction "GND_C12") (pintype "passive"))
      (node (ref "J1") (pin "C13") (pinfunction "GND_C13") (pintype "passive"))
      (node (ref "J1") (pin "C16") (pinfunction "GND_C16") (pintype "passive"))
      (node (ref "J1") (pin "C17") (pinfunction "GND_C17") (pintype "passive"))
      (node (ref "J1") (pin "C20") (pinfunction "GND_C20") (pintype "passive"))
      (node (ref "J1") (pin "C21") (pinfunction "GND_C21") (pintype "passive"))
      (node (ref "J1") (pin "C24") (pinfunction "GND_C24") (pintype "passive"))
      (node (ref "J1") (pin "C25") (pinfunction "GND_C25") (pintype "passive"))
      (node (ref "J1") (pin "C28") (pinfunction "GND_C28") (pintype "passive"))
      (node (ref "J1") (pin "C29") (pinfunction "GND_C29") (pintype "passive"))
      (node (ref "J1") (pin "C32") (pinfunction "GND_C32") (pintype "passive"))
      (node (ref "J1") (pin "C33") (pinfunction "GND_C33") (pintype "passive"))
      (node (ref "J1") (pin "C36") (pinfunction "GND_C36") (pintype "passive"))
      (node (ref "J1") (pin "C38") (pinfunction "GND_C38") (pintype "passive"))
      (node (ref "J1") (pin "C4") (pinfunction "GND_C4") (pintype "passive"))
      (node (ref "J1") (pin "C40") (pinfunction "GND_C40") (pintype "passive"))
      (node (ref "J1") (pin "C5") (pinfunction "GND_C5") (pintype "passive"))
      (node (ref "J1") (pin "C8") (pinfunction "GND_C8") (pintype "passive"))
      (node (ref "J1") (pin "C9") (pinfunction "GND_C9") (pintype "passive"))
      (node (ref "J1") (pin "D10") (pinfunction "GND_D10") (pintype "passive"))
      (node (ref "J1") (pin "D13") (pinfunction "GND_D13") (pintype "passive"))
      (node (ref "J1") (pin "D16") (pinfunction "GND_D16") (pintype "passive"))
      (node (ref "J1") (pin "D19") (pinfunction "GND_D19") (pintype "passive"))
      (node (ref "J1") (pin "D2") (pinfunction "GND_D2") (pintype "passive"))
      (node (ref "J1") (pin "D22") (pinfunction "GND_D22") (pintype "passive"))
      (node (ref "J1") (pin "D25") (pinfunction "GND_D25") (pintype "passive"))
      (node (ref "J1") (pin "D28") (pinfunction "GND_D28") (pintype "passive"))
      (node (ref "J1") (pin "D3") (pinfunction "GND_D3") (pintype "passive"))
      (node (ref "J1") (pin "D37") (pinfunction "GND_D37") (pintype "passive"))
      (node (ref "J1") (pin "D39") (pinfunction "GND_D39") (pintype "passive"))
      (node (ref "J1") (pin "D6") (pinfunction "GND_D6") (pintype "passive"))
      (node (ref "J1") (pin "D7") (pinfunction "GND_D7") (pintype "passive"))
      (node (ref "J1") (pin "E1") (pinfunction "GND_E1") (pintype "passive"))
      (node (ref "J1") (pin "E11") (pinfunction "GND_E11") (pintype "passive"))
      (node (ref "J1") (pin "E14") (pinfunction "GND_E14") (pintype "passive"))
      (node (ref "J1") (pin "E17") (pinfunction "GND_E17") (pintype "passive"))
      (node (ref "J1") (pin "E20") (pinfunction "GND_E20") (pintype "passive"))
      (node (ref "J1") (pin "E23") (pinfunction "GND_E23") (pintype "passive"))
      (node (ref "J1") (pin "E26") (pinfunction "GND_E26") (pintype "passive"))
      (node (ref "J1") (pin "E29") (pinfunction "GND_E29") (pintype "passive"))
      (node (ref "J1") (pin "E32") (pinfunction "GND_E32") (pintype "passive"))
      (node (ref "J1") (pin "E35") (pinfunction "GND_E35") (pintype "passive"))
      (node (ref "J1") (pin "E38") (pinfunction "GND_E38") (pintype "passive"))
      (node (ref "J1") (pin "E4") (pinfunction "GND_E4") (pintype "passive"))
      (node (ref "J1") (pin "E40") (pinfunction "GND_E40") (pintype "passive"))
      (node (ref "J1") (pin "E5") (pinfunction "GND_E5") (pintype "passive"))
      (node (ref "J1") (pin "E8") (pinfunction "GND_E8") (pintype "passive"))
      (node (ref "J1") (pin "F12") (pinfunction "GND_F12") (pintype "passive"))
      (node (ref "J1") (pin "F15") (pinfunction "GND_F15") (pintype "passive"))
      (node (ref "J1") (pin "F18") (pinfunction "GND_F18") (pintype "passive"))
      (node (ref "J1") (pin "F2") (pinfunction "GND_F2") (pintype "passive"))
      (node (ref "J1") (pin "F21") (pinfunction "GND_F21") (pintype "passive"))
      (node (ref "J1") (pin "F24") (pinfunction "GND_F24") (pintype "passive"))
      (node (ref "J1") (pin "F27") (pinfunction "GND_F27") (pintype "passive"))
      (node (ref "J1") (pin "F3") (pinfunction "GND_F3") (pintype "passive"))
      (node (ref "J1") (pin "F30") (pinfunction "GND_F30") (pintype "passive"))
      (node (ref "J1") (pin "F33") (pinfunction "GND_F33") (pintype "passive"))
      (node (ref "J1") (pin "F36") (pinfunction "GND_F36") (pintype "passive"))
      (node (ref "J1") (pin "F39") (pinfunction "GND_F39") (pintype "passive"))
      (node (ref "J1") (pin "F6") (pinfunction "GND_F6") (pintype "passive"))
      (node (ref "J1") (pin "F9") (pinfunction "GND_F9") (pintype "passive"))
      (node (ref "J1") (pin "G1") (pinfunction "GND_G1") (pintype "passive"))
      (node (ref "J1") (pin "G11") (pinfunction "GND_G11") (pintype "passive"))
      (node (ref "J1") (pin "G14") (pinfunction "GND_G14") (pintype "passive"))
      (node (ref "J1") (pin "G17") (pinfunction "GND_G17") (pintype "passive"))
      (node (ref "J1") (pin "G20") (pinfunction "GND_G20") (pintype "passive"))
      (node (ref "J1") (pin "G23") (pinfunction "GND_G23") (pintype "passive"))
      (node (ref "J1") (pin "G26") (pinfunction "GND_G26") (pintype "passive"))
      (node (ref "J1") (pin "G29") (pinfunction "GND_G29") (pintype "passive"))
      (node (ref "J1") (pin "G32") (pinfunction "GND_G32") (pintype "passive"))
      (node (ref "J1") (pin "G35") (pinfunction "GND_G35") (pintype "passive"))
      (node (ref "J1") (pin "G38") (pinfunction "GND_G38") (pintype "passive"))
      (node (ref "J1") (pin "G4") (pinfunction "GND_G4") (pintype "passive"))
      (node (ref "J1") (pin "G40") (pinfunction "GND_G40") (pintype "passive"))
      (node (ref "J1") (pin "G5") (pinfunction "GND_G5") (pintype "passive"))
      (node (ref "J1") (pin "G8") (pinfunction "GND_G8") (pintype "passive"))
      (node (ref "J1") (pin "H12") (pinfunction "GND_H12") (pintype "passive"))
      (node (ref "J1") (pin "H15") (pinfunction "GND_H15") (pintype "passive"))
      (node (ref "J1") (pin "H18") (pinfunction "GND_H18") (pintype "passive"))
      (node (ref "J1") (pin "H21") (pinfunction "GND_H21") (pintype "passive"))
      (node (ref "J1") (pin "H24") (pinfunction "GND_H24") (pintype "passive"))
      (node (ref "J1") (pin "H27") (pinfunction "GND_H27") (pintype "passive"))
      (node (ref "J1") (pin "H3") (pinfunction "GND_H3") (pintype "passive"))
      (node (ref "J1") (pin "H30") (pinfunction "GND_H30") (pintype "passive"))
      (node (ref "J1") (pin "H33") (pinfunction "GND_H33") (pintype "passive"))
      (node (ref "J1") (pin "H36") (pinfunction "GND_H36") (pintype "passive"))
      (node (ref "J1") (pin "H39") (pinfunction "GND_H39") (pintype "passive"))
      (node (ref "J1") (pin "H6") (pinfunction "GND_H6") (pintype "passive"))
      (node (ref "J1") (pin "H9") (pinfunction "GND_H9") (pintype "passive"))
      (node (ref "J1") (pin "J1") (pinfunction "GND_J1") (pintype "passive"))
      (node (ref "J1") (pin "J11") (pinfunction "GND_J11") (pintype "passive"))
      (node (ref "J1") (pin "J14") (pinfunction "GND_J14") (pintype "passive"))
      (node (ref "J1") (pin "J17") (pinfunction "GND_J17") (pintype "passive"))
      (node (ref "J1") (pin "J20") (pinfunction "GND_J20") (pintype "passive"))
      (node (ref "J1") (pin "J23") (pinfunction "GND_J23") (pintype "passive"))
      (node (ref "J1") (pin "J26") (pinfunction "GND_J26") (pintype "passive"))
      (node (ref "J1") (pin "J29") (pinfunction "GND_J29") (pintype "passive"))
      (node (ref "J1") (pin "J32") (pinfunction "GND_J32") (pintype "passive"))
      (node (ref "J1") (pin "J35") (pinfunction "GND_J35") (pintype "passive"))
      (node (ref "J1") (pin "J38") (pinfunction "GND_J38") (pintype "passive"))
      (node (ref "J1") (pin "J4") (pinfunction "GND_J4") (pintype "passive"))
      (node (ref "J1") (pin "J40") (pinfunction "GND_J40") (pintype "passive"))
      (node (ref "J1") (pin "J5") (pinfunction "GND_J5") (pintype "passive"))
      (node (ref "J1") (pin "J8") (pinfunction "GND_J8") (pintype "passive"))
      (node (ref "J1") (pin "K12") (pinfunction "GND_K12") (pintype "passive"))
      (node (ref "J1") (pin "K15") (pinfunction "GND_K15") (pintype "passive"))
      (node (ref "J1") (pin "K18") (pinfunction "GND_K18") (pintype "passive"))
      (node (ref "J1") (pin "K2") (pinfunction "GND_K2") (pintype "passive"))
      (node (ref "J1") (pin "K21") (pinfunction "GND_K21") (pintype "passive"))
      (node (ref "J1") (pin "K24") (pinfunction "GND_K24") (pintype "passive"))
      (node (ref "J1") (pin "K27") (pinfunction "GND_K27") (pintype "passive"))
      (node (ref "J1") (pin "K3") (pinfunction "GND_K3") (pintype "passive"))
      (node (ref "J1") (pin "K30") (pinfunction "GND_K30") (pintype "passive"))
      (node (ref "J1") (pin "K33") (pinfunction "GND_K33") (pintype "passive"))
      (node (ref "J1") (pin "K36") (pinfunction "GND_K36") (pintype "passive"))
      (node (ref "J1") (pin "K39") (pinfunction "GND_K39") (pintype "passive"))
      (node (ref "J1") (pin "K6") (pinfunction "GND_K6") (pintype "passive"))
      (node (ref "J1") (pin "K9") (pinfunction "GND_K9") (pintype "passive"))
      (node (ref "R5") (pin "2") (pinfunction "2_2") (pintype "passive"))
    )
    (net (code "128") (name "Net-(C1-Pad1)") (class "Default")
      (node (ref "C1") (pin "1") (pinfunction "1_1") (pintype "passive"))
      (node (ref "R2") (pin "1") (pinfunction "1_1") (pintype "passive"))
    )
    (net (code "129") (name "Net-(IC1-B1)") (class "Default")
      (node (ref "IC1") (pin "5") (pinfunction "B1_5") (pintype "passive"))
      (node (ref "IC2") (pin "3") (pinfunction "A1_3") (pintype "bidirectional"))
      (node (ref "IC2") (pin "4") (pinfunction "A2_4") (pintype "bidirectional"))
      (node (ref "IC2") (pin "5") (pinfunction "A3_5") (pintype "bidirectional"))
      (node (ref "IC2") (pin "6") (pinfunction "A4_6") (pintype "bidirectional"))
    )
    (net (code "130") (name "Net-(IC1-B2)") (class "Default")
      (node (ref "IC1") (pin "4") (pinfunction "B2_4") (pintype "passive"))
      (node (ref "IC2") (pin "10") (pinfunction "A8_10") (pintype "bidirectional"))
      (node (ref "IC2") (pin "7") (pinfunction "A5_7") (pintype "bidirectional"))
      (node (ref "IC2") (pin "8") (pinfunction "A6_8") (pintype "bidirectional"))
      (node (ref "IC2") (pin "9") (pinfunction "A7_9") (pintype "bidirectional"))
    )
    (net (code "131") (name "Net-(IC3-B1)") (class "Default")
      (node (ref "IC3") (pin "5") (pinfunction "B1_5") (pintype "passive"))
      (node (ref "IC4") (pin "3") (pinfunction "A1_3") (pintype "bidirectional"))
      (node (ref "IC4") (pin "4") (pinfunction "A2_4") (pintype "bidirectional"))
      (node (ref "IC4") (pin "5") (pinfunction "A3_5") (pintype "bidirectional"))
      (node (ref "IC4") (pin "6") (pinfunction "A4_6") (pintype "bidirectional"))
    )
    (net (code "132") (name "Net-(IC3-B2)") (class "Default")
      (node (ref "IC3") (pin "4") (pinfunction "B2_4") (pintype "passive"))
      (node (ref "IC4") (pin "10") (pinfunction "A8_10") (pintype "bidirectional"))
      (node (ref "IC4") (pin "7") (pinfunction "A5_7") (pintype "bidirectional"))
      (node (ref "IC4") (pin "8") (pinfunction "A6_8") (pintype "bidirectional"))
      (node (ref "IC4") (pin "9") (pinfunction "A7_9") (pintype "bidirectional"))
    )
    (net (code "133") (name "Net-(J1E-PRSNT_M2C_L)") (class "Default")
      (node (ref "J1") (pin "H2") (pinfunction "PRSNT_M2C_L_H2") (pintype "passive"))
      (node (ref "R5") (pin "1") (pinfunction "1_1") (pintype "passive"))
    )
    (net (code "134") (name "VCC3P3_1") (class "Default")
      (node (ref "C2") (pin "2") (pinfunction "2_2") (pintype "passive"))
      (node (ref "C3") (pin "2") (pinfunction "2_2") (pintype "passive"))
      (node (ref "C4") (pin "2") (pinfunction "2_2") (pintype "passive"))
      (node (ref "C5") (pin "2") (pinfunction "2_2") (pintype "passive"))
      (node (ref "C6") (pin "2") (pinfunction "2_2") (pintype "passive"))
      (node (ref "C7") (pin "2") (pinfunction "2_2") (pintype "passive"))
      (node (ref "C8") (pin "2") (pinfunction "2_2") (pintype "passive"))
      (node (ref "C9") (pin "2") (pinfunction "2_2") (pintype "passive"))
      (node (ref "IC1") (pin "1") (pinfunction "DIR2_1") (pintype "passive"))
      (node (ref "IC1") (pin "10") (pinfunction "DIR1_10") (pintype "passive"))
      (node (ref "IC1") (pin "6") (pinfunction "VCCB_6") (pintype "passive"))
      (node (ref "IC1") (pin "7") (pinfunction "VCCA_7") (pintype "passive"))
      (node (ref "IC2") (pin "1") (pinfunction "VCCA_1") (pintype "power_in"))
      (node (ref "IC2") (pin "2") (pinfunction "DIR_2") (pintype "input"))
      (node (ref "IC2") (pin "23") (pinfunction "VCCB_23") (pintype "power_in"))
      (node (ref "IC2") (pin "24") (pinfunction "VCCB_24") (pintype "power_in"))
      (node (ref "IC3") (pin "1") (pinfunction "DIR2_1") (pintype "passive"))
      (node (ref "IC3") (pin "10") (pinfunction "DIR1_10") (pintype "passive"))
      (node (ref "IC3") (pin "6") (pinfunction "VCCB_6") (pintype "passive"))
      (node (ref "IC3") (pin "7") (pinfunction "VCCA_7") (pintype "passive"))
      (node (ref "IC4") (pin "1") (pinfunction "VCCA_1") (pintype "power_in"))
      (node (ref "IC4") (pin "2") (pinfunction "DIR_2") (pintype "input"))
      (node (ref "IC4") (pin "23") (pinfunction "VCCB_23") (pintype "power_in"))
      (node (ref "IC4") (pin "24") (pinfunction "VCCB_24") (pintype "power_in"))
      (node (ref "R1") (pin "1") (pinfunction "1_1") (pintype "passive"))
      (node (ref "R3") (pin "1") (pinfunction "1_1") (pintype "passive"))
    )
    (net (code "135") (name "unconnected-(J1A-LA13_N-PadD18)") (class "Default")
      (node (ref "J1") (pin "D18") (pinfunction "LA13_N_D18") (pintype "passive+no_connect"))
    )
    (net (code "136") (name "unconnected-(J1A-LA16_N-PadG19)") (class "Default")
      (node (ref "J1") (pin "G19") (pinfunction "LA16_N_G19") (pintype "passive+no_connect"))
    )
    (net (code "137") (name "unconnected-(J1A-LA18_CC_N-PadC23)") (class "Default")
      (node (ref "J1") (pin "C23") (pinfunction "LA18_CC_N_C23") (pintype "passive+no_connect"))
    )
    (net (code "138") (name "unconnected-(J1A-LA18_CC_P-PadC22)") (class "Default")
      (node (ref "J1") (pin "C22") (pinfunction "LA18_CC_P_C22") (pintype "passive+no_connect"))
    )
    (net (code "139") (name "unconnected-(J1A-LA19_P-PadH22)") (class "Default")
      (node (ref "J1") (pin "H22") (pinfunction "LA19_P_H22") (pintype "passive+no_connect"))
    )
    (net (code "140") (name "unconnected-(J1A-LA20_N-PadG22)") (class "Default")
      (node (ref "J1") (pin "G22") (pinfunction "LA20_N_G22") (pintype "passive+no_connect"))
    )
    (net (code "141") (name "unconnected-(J1A-LA20_P-PadG21)") (class "Default")
      (node (ref "J1") (pin "G21") (pinfunction "LA20_P_G21") (pintype "passive+no_connect"))
    )
    (net (code "142") (name "unconnected-(J1A-LA29_N-PadG31)") (class "Default")
      (node (ref "J1") (pin "G31") (pinfunction "LA29_N_G31") (pintype "passive+no_connect"))
    )
    (net (code "143") (name "unconnected-(J1B-HA00_CC_N-PadF5)") (class "Default")
      (node (ref "J1") (pin "F5") (pinfunction "HA00_CC_N_F5") (pintype "passive+no_connect"))
    )
    (net (code "144") (name "unconnected-(J1B-HA00_CC_P-PadF4)") (class "Default")
      (node (ref "J1") (pin "F4") (pinfunction "HA00_CC_P_F4") (pintype "passive+no_connect"))
    )
    (net (code "145") (name "unconnected-(J1B-HA01_CC_N-PadE3)") (class "Default")
      (node (ref "J1") (pin "E3") (pinfunction "HA01_CC_N_E3") (pintype "passive+no_connect"))
    )
    (net (code "146") (name "unconnected-(J1B-HA01_CC_P-PadE2)") (class "Default")
      (node (ref "J1") (pin "E2") (pinfunction "HA01_CC_P_E2") (pintype "passive+no_connect"))
    )
    (net (code "147") (name "unconnected-(J1B-HA02_N-PadK8)") (class "Default")
      (node (ref "J1") (pin "K8") (pinfunction "HA02_N_K8") (pintype "passive+no_connect"))
    )
    (net (code "148") (name "unconnected-(J1B-HA02_P-PadK7)") (class "Default")
      (node (ref "J1") (pin "K7") (pinfunction "HA02_P_K7") (pintype "passive+no_connect"))
    )
    (net (code "149") (name "unconnected-(J1B-HA03_N-PadJ7)") (class "Default")
      (node (ref "J1") (pin "J7") (pinfunction "HA03_N_J7") (pintype "passive+no_connect"))
    )
    (net (code "150") (name "unconnected-(J1B-HA03_P-PadJ6)") (class "Default")
      (node (ref "J1") (pin "J6") (pinfunction "HA03_P_J6") (pintype "passive+no_connect"))
    )
    (net (code "151") (name "unconnected-(J1B-HA04_N-PadF8)") (class "Default")
      (node (ref "J1") (pin "F8") (pinfunction "HA04_N_F8") (pintype "passive+no_connect"))
    )
    (net (code "152") (name "unconnected-(J1B-HA04_P-PadF7)") (class "Default")
      (node (ref "J1") (pin "F7") (pinfunction "HA04_P_F7") (pintype "passive+no_connect"))
    )
    (net (code "153") (name "unconnected-(J1B-HA05_N-PadE7)") (class "Default")
      (node (ref "J1") (pin "E7") (pinfunction "HA05_N_E7") (pintype "passive+no_connect"))
    )
    (net (code "154") (name "unconnected-(J1B-HA05_P-PadE6)") (class "Default")
      (node (ref "J1") (pin "E6") (pinfunction "HA05_P_E6") (pintype "passive+no_connect"))
    )
    (net (code "155") (name "unconnected-(J1B-HA06_N-PadK11)") (class "Default")
      (node (ref "J1") (pin "K11") (pinfunction "HA06_N_K11") (pintype "passive+no_connect"))
    )
    (net (code "156") (name "unconnected-(J1B-HA06_P-PadK10)") (class "Default")
      (node (ref "J1") (pin "K10") (pinfunction "HA06_P_K10") (pintype "passive+no_connect"))
    )
    (net (code "157") (name "unconnected-(J1B-HA07_N-PadJ10)") (class "Default")
      (node (ref "J1") (pin "J10") (pinfunction "HA07_N_J10") (pintype "passive+no_connect"))
    )
    (net (code "158") (name "unconnected-(J1B-HA07_P-PadJ9)") (class "Default")
      (node (ref "J1") (pin "J9") (pinfunction "HA07_P_J9") (pintype "passive+no_connect"))
    )
    (net (code "159") (name "unconnected-(J1B-HA08_N-PadF11)") (class "Default")
      (node (ref "J1") (pin "F11") (pinfunction "HA08_N_F11") (pintype "passive+no_connect"))
    )
    (net (code "160") (name "unconnected-(J1B-HA08_P-PadF10)") (class "Default")
      (node (ref "J1") (pin "F10") (pinfunction "HA08_P_F10") (pintype "passive+no_connect"))
    )
    (net (code "161") (name "unconnected-(J1B-HA09_N-PadE10)") (class "Default")
      (node (ref "J1") (pin "E10") (pinfunction "HA09_N_E10") (pintype "passive+no_connect"))
    )
    (net (code "162") (name "unconnected-(J1B-HA09_P-PadE9)") (class "Default")
      (node (ref "J1") (pin "E9") (pinfunction "HA09_P_E9") (pintype "passive+no_connect"))
    )
    (net (code "163") (name "unconnected-(J1B-HA10_N-PadK14)") (class "Default")
      (node (ref "J1") (pin "K14") (pinfunction "HA10_N_K14") (pintype "passive+no_connect"))
    )
    (net (code "164") (name "unconnected-(J1B-HA10_P-PadK13)") (class "Default")
      (node (ref "J1") (pin "K13") (pinfunction "HA10_P_K13") (pintype "passive+no_connect"))
    )
    (net (code "165") (name "unconnected-(J1B-HA11_N-PadJ13)") (class "Default")
      (node (ref "J1") (pin "J13") (pinfunction "HA11_N_J13") (pintype "passive+no_connect"))
    )
    (net (code "166") (name "unconnected-(J1B-HA11_P-PadJ12)") (class "Default")
      (node (ref "J1") (pin "J12") (pinfunction "HA11_P_J12") (pintype "passive+no_connect"))
    )
    (net (code "167") (name "unconnected-(J1B-HA12_N-PadF14)") (class "Default")
      (node (ref "J1") (pin "F14") (pinfunction "HA12_N_F14") (pintype "passive+no_connect"))
    )
    (net (code "168") (name "unconnected-(J1B-HA12_P-PadF13)") (class "Default")
      (node (ref "J1") (pin "F13") (pinfunction "HA12_P_F13") (pintype "passive+no_connect"))
    )
    (net (code "169") (name "unconnected-(J1B-HA13_N-PadE13)") (class "Default")
      (node (ref "J1") (pin "E13") (pinfunction "HA13_N_E13") (pintype "passive+no_connect"))
    )
    (net (code "170") (name "unconnected-(J1B-HA13_P-PadE12)") (class "Default")
      (node (ref "J1") (pin "E12") (pinfunction "HA13_P_E12") (pintype "passive+no_connect"))
    )
    (net (code "171") (name "unconnected-(J1B-HA14_N-PadJ16)") (class "Default")
      (node (ref "J1") (pin "J16") (pinfunction "HA14_N_J16") (pintype "passive+no_connect"))
    )
    (net (code "172") (name "unconnected-(J1B-HA14_P-PadJ15)") (class "Default")
      (node (ref "J1") (pin "J15") (pinfunction "HA14_P_J15") (pintype "passive+no_connect"))
    )
    (net (code "173") (name "unconnected-(J1B-HA15_N-PadF17)") (class "Default")
      (node (ref "J1") (pin "F17") (pinfunction "HA15_N_F17") (pintype "passive+no_connect"))
    )
    (net (code "174") (name "unconnected-(J1B-HA15_P-PadF16)") (class "Default")
      (node (ref "J1") (pin "F16") (pinfunction "HA15_P_F16") (pintype "passive+no_connect"))
    )
    (net (code "175") (name "unconnected-(J1B-HA16_N-PadE16)") (class "Default")
      (node (ref "J1") (pin "E16") (pinfunction "HA16_N_E16") (pintype "passive+no_connect"))
    )
    (net (code "176") (name "unconnected-(J1B-HA16_P-PadE15)") (class "Default")
      (node (ref "J1") (pin "E15") (pinfunction "HA16_P_E15") (pintype "passive+no_connect"))
    )
    (net (code "177") (name "unconnected-(J1B-HA17_CC_N-PadK17)") (class "Default")
      (node (ref "J1") (pin "K17") (pinfunction "HA17_CC_N_K17") (pintype "passive+no_connect"))
    )
    (net (code "178") (name "unconnected-(J1B-HA17_CC_P-PadK16)") (class "Default")
      (node (ref "J1") (pin "K16") (pinfunction "HA17_CC_P_K16") (pintype "passive+no_connect"))
    )
    (net (code "179") (name "unconnected-(J1B-HA18_N-PadJ19)") (class "Default")
      (node (ref "J1") (pin "J19") (pinfunction "HA18_N_J19") (pintype "passive+no_connect"))
    )
    (net (code "180") (name "unconnected-(J1B-HA18_P-PadJ18)") (class "Default")
      (node (ref "J1") (pin "J18") (pinfunction "HA18_P_J18") (pintype "passive+no_connect"))
    )
    (net (code "181") (name "unconnected-(J1B-HA19_N-PadF20)") (class "Default")
      (node (ref "J1") (pin "F20") (pinfunction "HA19_N_F20") (pintype "passive+no_connect"))
    )
    (net (code "182") (name "unconnected-(J1B-HA19_P-PadF19)") (class "Default")
      (node (ref "J1") (pin "F19") (pinfunction "HA19_P_F19") (pintype "passive+no_connect"))
    )
    (net (code "183") (name "unconnected-(J1B-HA20_N-PadE19)") (class "Default")
      (node (ref "J1") (pin "E19") (pinfunction "HA20_N_E19") (pintype "passive+no_connect"))
    )
    (net (code "184") (name "unconnected-(J1B-HA20_P-PadE18)") (class "Default")
      (node (ref "J1") (pin "E18") (pinfunction "HA20_P_E18") (pintype "passive+no_connect"))
    )
    (net (code "185") (name "unconnected-(J1B-HA21_N-PadK20)") (class "Default")
      (node (ref "J1") (pin "K20") (pinfunction "HA21_N_K20") (pintype "passive+no_connect"))
    )
    (net (code "186") (name "unconnected-(J1B-HA21_P-PadK19)") (class "Default")
      (node (ref "J1") (pin "K19") (pinfunction "HA21_P_K19") (pintype "passive+no_connect"))
    )
    (net (code "187") (name "unconnected-(J1B-HA22_N-PadJ22)") (class "Default")
      (node (ref "J1") (pin "J22") (pinfunction "HA22_N_J22") (pintype "passive+no_connect"))
    )
    (net (code "188") (name "unconnected-(J1B-HA22_P-PadJ21)") (class "Default")
      (node (ref "J1") (pin "J21") (pinfunction "HA22_P_J21") (pintype "passive+no_connect"))
    )
    (net (code "189") (name "unconnected-(J1B-HA23_N-PadK23)") (class "Default")
      (node (ref "J1") (pin "K23") (pinfunction "HA23_N_K23") (pintype "passive+no_connect"))
    )
    (net (code "190") (name "unconnected-(J1B-HA23_P-PadK22)") (class "Default")
      (node (ref "J1") (pin "K22") (pinfunction "HA23_P_K22") (pintype "passive+no_connect"))
    )
    (net (code "191") (name "unconnected-(J1C-HB00_CC_N-PadK26)") (class "Default")
      (node (ref "J1") (pin "K26") (pinfunction "HB00_CC_N_K26") (pintype "passive+no_connect"))
    )
    (net (code "192") (name "unconnected-(J1C-HB00_CC_P-PadK25)") (class "Default")
      (node (ref "J1") (pin "K25") (pinfunction "HB00_CC_P_K25") (pintype "passive+no_connect"))
    )
    (net (code "193") (name "unconnected-(J1C-HB01_N-PadJ25)") (class "Default")
      (node (ref "J1") (pin "J25") (pinfunction "HB01_N_J25") (pintype "passive+no_connect"))
    )
    (net (code "194") (name "unconnected-(J1C-HB01_P-PadJ24)") (class "Default")
      (node (ref "J1") (pin "J24") (pinfunction "HB01_P_J24") (pintype "passive+no_connect"))
    )
    (net (code "195") (name "unconnected-(J1C-HB02_N-PadF23)") (class "Default")
      (node (ref "J1") (pin "F23") (pinfunction "HB02_N_F23") (pintype "passive+no_connect"))
    )
    (net (code "196") (name "unconnected-(J1C-HB02_P-PadF22)") (class "Default")
      (node (ref "J1") (pin "F22") (pinfunction "HB02_P_F22") (pintype "passive+no_connect"))
    )
    (net (code "197") (name "unconnected-(J1C-HB03_N-PadE22)") (class "Default")
      (node (ref "J1") (pin "E22") (pinfunction "HB03_N_E22") (pintype "passive+no_connect"))
    )
    (net (code "198") (name "unconnected-(J1C-HB03_P-PadE21)") (class "Default")
      (node (ref "J1") (pin "E21") (pinfunction "HB03_P_E21") (pintype "passive+no_connect"))
    )
    (net (code "199") (name "unconnected-(J1C-HB04_N-PadF26)") (class "Default")
      (node (ref "J1") (pin "F26") (pinfunction "HB04_N_F26") (pintype "passive+no_connect"))
    )
    (net (code "200") (name "unconnected-(J1C-HB04_P-PadF25)") (class "Default")
      (node (ref "J1") (pin "F25") (pinfunction "HB04_P_F25") (pintype "passive+no_connect"))
    )
    (net (code "201") (name "unconnected-(J1C-HB05_N-PadE25)") (class "Default")
      (node (ref "J1") (pin "E25") (pinfunction "HB05_N_E25") (pintype "passive+no_connect"))
    )
    (net (code "202") (name "unconnected-(J1C-HB05_P-PadE24)") (class "Default")
      (node (ref "J1") (pin "E24") (pinfunction "HB05_P_E24") (pintype "passive+no_connect"))
    )
    (net (code "203") (name "unconnected-(J1C-HB06_CC_N-PadK29)") (class "Default")
      (node (ref "J1") (pin "K29") (pinfunction "HB06_CC_N_K29") (pintype "passive+no_connect"))
    )
    (net (code "204") (name "unconnected-(J1C-HB06_CC_P-PadK28)") (class "Default")
      (node (ref "J1") (pin "K28") (pinfunction "HB06_CC_P_K28") (pintype "passive+no_connect"))
    )
    (net (code "205") (name "unconnected-(J1C-HB07_N-PadJ28)") (class "Default")
      (node (ref "J1") (pin "J28") (pinfunction "HB07_N_J28") (pintype "passive+no_connect"))
    )
    (net (code "206") (name "unconnected-(J1C-HB07_P-PadJ27)") (class "Default")
      (node (ref "J1") (pin "J27") (pinfunction "HB07_P_J27") (pintype "passive+no_connect"))
    )
    (net (code "207") (name "unconnected-(J1C-HB08_N-PadF29)") (class "Default")
      (node (ref "J1") (pin "F29") (pinfunction "HB08_N_F29") (pintype "passive+no_connect"))
    )
    (net (code "208") (name "unconnected-(J1C-HB08_P-PadF28)") (class "Default")
      (node (ref "J1") (pin "F28") (pinfunction "HB08_P_F28") (pintype "passive+no_connect"))
    )
    (net (code "209") (name "unconnected-(J1C-HB09_N-PadE28)") (class "Default")
      (node (ref "J1") (pin "E28") (pinfunction "HB09_N_E28") (pintype "passive+no_connect"))
    )
    (net (code "210") (name "unconnected-(J1C-HB09_P-PadE27)") (class "Default")
      (node (ref "J1") (pin "E27") (pinfunction "HB09_P_E27") (pintype "passive+no_connect"))
    )
    (net (code "211") (name "unconnected-(J1C-HB10_N-PadK32)") (class "Default")
      (node (ref "J1") (pin "K32") (pinfunction "HB10_N_K32") (pintype "passive+no_connect"))
    )
    (net (code "212") (name "unconnected-(J1C-HB10_P-PadK31)") (class "Default")
      (node (ref "J1") (pin "K31") (pinfunction "HB10_P_K31") (pintype "passive+no_connect"))
    )
    (net (code "213") (name "unconnected-(J1C-HB11_N-PadJ31)") (class "Default")
      (node (ref "J1") (pin "J31") (pinfunction "HB11_N_J31") (pintype "passive+no_connect"))
    )
    (net (code "214") (name "unconnected-(J1C-HB11_P-PadJ30)") (class "Default")
      (node (ref "J1") (pin "J30") (pinfunction "HB11_P_J30") (pintype "passive+no_connect"))
    )
    (net (code "215") (name "unconnected-(J1C-HB12_N-PadF32)") (class "Default")
      (node (ref "J1") (pin "F32") (pinfunction "HB12_N_F32") (pintype "passive+no_connect"))
    )
    (net (code "216") (name "unconnected-(J1C-HB12_P-PadF31)") (class "Default")
      (node (ref "J1") (pin "F31") (pinfunction "HB12_P_F31") (pintype "passive+no_connect"))
    )
    (net (code "217") (name "unconnected-(J1C-HB13_N-PadE31)") (class "Default")
      (node (ref "J1") (pin "E31") (pinfunction "HB13_N_E31") (pintype "passive+no_connect"))
    )
    (net (code "218") (name "unconnected-(J1C-HB13_P-PadE30)") (class "Default")
      (node (ref "J1") (pin "E30") (pinfunction "HB13_P_E30") (pintype "passive+no_connect"))
    )
    (net (code "219") (name "unconnected-(J1C-HB14_N-PadK35)") (class "Default")
      (node (ref "J1") (pin "K35") (pinfunction "HB14_N_K35") (pintype "passive+no_connect"))
    )
    (net (code "220") (name "unconnected-(J1C-HB14_P-PadK34)") (class "Default")
      (node (ref "J1") (pin "K34") (pinfunction "HB14_P_K34") (pintype "passive+no_connect"))
    )
    (net (code "221") (name "unconnected-(J1C-HB15_N-PadJ34)") (class "Default")
      (node (ref "J1") (pin "J34") (pinfunction "HB15_N_J34") (pintype "passive+no_connect"))
    )
    (net (code "222") (name "unconnected-(J1C-HB15_P-PadJ33)") (class "Default")
      (node (ref "J1") (pin "J33") (pinfunction "HB15_P_J33") (pintype "passive+no_connect"))
    )
    (net (code "223") (name "unconnected-(J1C-HB16_N-PadF35)") (class "Default")
      (node (ref "J1") (pin "F35") (pinfunction "HB16_N_F35") (pintype "passive+no_connect"))
    )
    (net (code "224") (name "unconnected-(J1C-HB16_P-PadF34)") (class "Default")
      (node (ref "J1") (pin "F34") (pinfunction "HB16_P_F34") (pintype "passive+no_connect"))
    )
    (net (code "225") (name "unconnected-(J1C-HB17_CC_N-PadK38)") (class "Default")
      (node (ref "J1") (pin "K38") (pinfunction "HB17_CC_N_K38") (pintype "passive+no_connect"))
    )
    (net (code "226") (name "unconnected-(J1C-HB17_CC_P-PadK37)") (class "Default")
      (node (ref "J1") (pin "K37") (pinfunction "HB17_CC_P_K37") (pintype "passive+no_connect"))
    )
    (net (code "227") (name "unconnected-(J1C-HB18_N-PadJ37)") (class "Default")
      (node (ref "J1") (pin "J37") (pinfunction "HB18_N_J37") (pintype "passive+no_connect"))
    )
    (net (code "228") (name "unconnected-(J1C-HB18_P-PadJ36)") (class "Default")
      (node (ref "J1") (pin "J36") (pinfunction "HB18_P_J36") (pintype "passive+no_connect"))
    )
    (net (code "229") (name "unconnected-(J1C-HB19_N-PadE34)") (class "Default")
      (node (ref "J1") (pin "E34") (pinfunction "HB19_N_E34") (pintype "passive+no_connect"))
    )
    (net (code "230") (name "unconnected-(J1C-HB19_P-PadE33)") (class "Default")
      (node (ref "J1") (pin "E33") (pinfunction "HB19_P_E33") (pintype "passive+no_connect"))
    )
    (net (code "231") (name "unconnected-(J1C-HB20_N-PadF38)") (class "Default")
      (node (ref "J1") (pin "F38") (pinfunction "HB20_N_F38") (pintype "passive+no_connect"))
    )
    (net (code "232") (name "unconnected-(J1C-HB20_P-PadF37)") (class "Default")
      (node (ref "J1") (pin "F37") (pinfunction "HB20_P_F37") (pintype "passive+no_connect"))
    )
    (net (code "233") (name "unconnected-(J1C-HB21_N-PadE37)") (class "Default")
      (node (ref "J1") (pin "E37") (pinfunction "HB21_N_E37") (pintype "passive+no_connect"))
    )
    (net (code "234") (name "unconnected-(J1C-HB21_P-PadE36)") (class "Default")
      (node (ref "J1") (pin "E36") (pinfunction "HB21_P_E36") (pintype "passive+no_connect"))
    )
    (net (code "235") (name "unconnected-(J1D-DP8_C2M_N-PadB29)") (class "Default")
      (node (ref "J1") (pin "B29") (pinfunction "DP8_C2M_N_B29") (pintype "passive+no_connect"))
    )
    (net (code "236") (name "unconnected-(J1D-DP8_C2M_P-PadB28)") (class "Default")
      (node (ref "J1") (pin "B28") (pinfunction "DP8_C2M_P_B28") (pintype "passive+no_connect"))
    )
    (net (code "237") (name "unconnected-(J1D-DP8_M2C_N-PadB9)") (class "Default")
      (node (ref "J1") (pin "B9") (pinfunction "DP8_M2C_N_B9") (pintype "passive+no_connect"))
    )
    (net (code "238") (name "unconnected-(J1D-DP8_M2C_P-PadB8)") (class "Default")
      (node (ref "J1") (pin "B8") (pinfunction "DP8_M2C_P_B8") (pintype "passive+no_connect"))
    )
    (net (code "239") (name "unconnected-(J1D-DP9_C2M_N-PadB25)") (class "Default")
      (node (ref "J1") (pin "B25") (pinfunction "DP9_C2M_N_B25") (pintype "passive+no_connect"))
    )
    (net (code "240") (name "unconnected-(J1D-DP9_C2M_P-PadB24)") (class "Default")
      (node (ref "J1") (pin "B24") (pinfunction "DP9_C2M_P_B24") (pintype "passive+no_connect"))
    )
    (net (code "241") (name "unconnected-(J1D-DP9_M2C_N-PadB5)") (class "Default")
      (node (ref "J1") (pin "B5") (pinfunction "DP9_M2C_N_B5") (pintype "passive+no_connect"))
    )
    (net (code "242") (name "unconnected-(J1D-DP9_M2C_P-PadB4)") (class "Default")
      (node (ref "J1") (pin "B4") (pinfunction "DP9_M2C_P_B4") (pintype "passive+no_connect"))
    )
    (net (code "243") (name "unconnected-(J1E-CLK0_M2C_N-PadH5)") (class "Default")
      (node (ref "J1") (pin "H5") (pinfunction "CLK0_M2C_N_H5") (pintype "passive+no_connect"))
    )
    (net (code "244") (name "unconnected-(J1E-CLK0_M2C_P-PadH4)") (class "Default")
      (node (ref "J1") (pin "H4") (pinfunction "CLK0_M2C_P_H4") (pintype "passive+no_connect"))
    )
    (net (code "245") (name "unconnected-(J1E-CLK1_C2M_N-PadJ3)") (class "Default")
      (node (ref "J1") (pin "J3") (pinfunction "CLK1_C2M_N_J3") (pintype "passive+no_connect"))
    )
    (net (code "246") (name "unconnected-(J1E-CLK1_C2M_P-PadJ2)") (class "Default")
      (node (ref "J1") (pin "J2") (pinfunction "CLK1_C2M_P_J2") (pintype "passive+no_connect"))
    )
    (net (code "247") (name "unconnected-(J1E-CLK1_M2C_N-PadK5)") (class "Default")
      (node (ref "J1") (pin "K5") (pinfunction "CLK1_M2C_N_K5") (pintype "passive+no_connect"))
    )
    (net (code "248") (name "unconnected-(J1E-CLK1_M2C_P-PadK4)") (class "Default")
      (node (ref "J1") (pin "K4") (pinfunction "CLK1_M2C_P_K4") (pintype "passive+no_connect"))
    )
    (net (code "249") (name "unconnected-(J1E-PG_C2M-PadD1)") (class "Default")
      (node (ref "J1") (pin "D1") (pinfunction "PG_C2M_D1") (pintype "passive+no_connect"))
    )
    (net (code "250") (name "unconnected-(J1E-PG_M2C-PadF1)") (class "Default")
      (node (ref "J1") (pin "F1") (pinfunction "PG_M2C_F1") (pintype "passive+no_connect"))
    )
    (net (code "251") (name "unconnected-(J1E-RES0-PadB40)") (class "Default")
      (node (ref "J1") (pin "B40") (pinfunction "RES0_B40") (pintype "passive+no_connect"))
    )
    (net (code "252") (name "unconnected-(J1E-RES1-PadB1)") (class "Default")
      (node (ref "J1") (pin "B1") (pinfunction "RES1_B1") (pintype "passive+no_connect"))
    )
    (net (code "253") (name "unconnected-(J1E-TRST_L-PadD34)") (class "Default")
      (node (ref "J1") (pin "D34") (pinfunction "TRST_L_D34") (pintype "passive+no_connect"))
    )
    (net (code "254") (name "unconnected-(J1F-VIO_B_M2C-PadJ39)") (class "Default")
      (node (ref "J1") (pin "J39") (pinfunction "VIO_B_M2C_J39") (pintype "passive+no_connect"))
    )
    (net (code "255") (name "unconnected-(J1F-VIO_B_M2C-PadK40)") (class "Default")
      (node (ref "J1") (pin "K40") (pinfunction "VIO_B_M2C_K40") (pintype "passive+no_connect"))
    )
    (net (code "256") (name "unconnected-(J1F-VREF_A_M2C-PadH1)") (class "Default")
      (node (ref "J1") (pin "H1") (pinfunction "VREF_A_M2C_H1") (pintype "passive+no_connect"))
    )
    (net (code "257") (name "unconnected-(J1F-VREF_B_M2C-PadK1)") (class "Default")
      (node (ref "J1") (pin "K1") (pinfunction "VREF_B_M2C_K1") (pintype "passive+no_connect"))
    )
  )
)
